# LCD-Shield.net
KiCad netlist of a schematic drawn in EAGLE
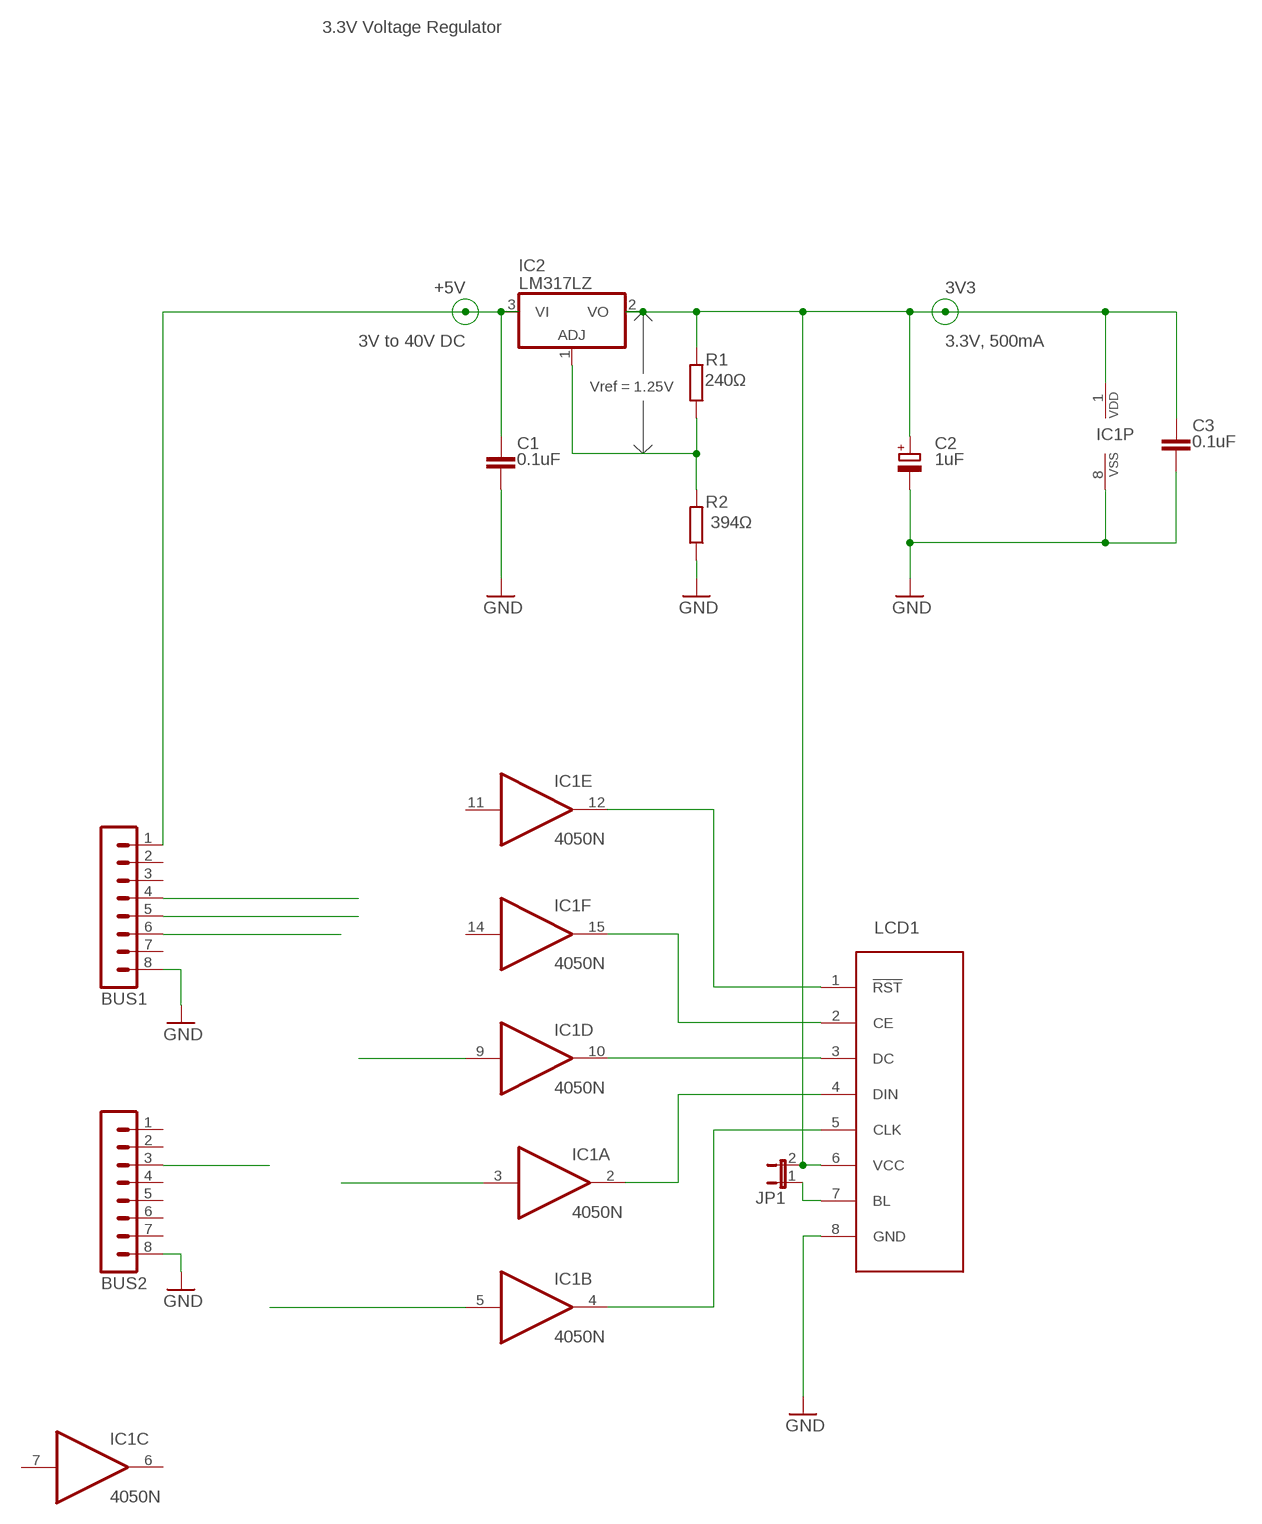
[diagram p0: schematic, sheet 1]

(export (version "E")
  (design (tool "Eeschema 10.0.6"))
  (components
    (comp (ref "BUS1")
      (value "MA08-1")
      (footprint "eagle-import:MA08-1")
      (libsource (lib "eagle-import") (part "MA08-1"))
    )
    (comp (ref "BUS2")
      (value "MA08-1")
      (footprint "eagle-import:MA08-1")
      (libsource (lib "eagle-import") (part "MA08-1"))
    )
    (comp (ref "C1")
      (value "0.1uF")
      (footprint "eagle-import:C025-024X044")
      (libsource (lib "eagle-import") (part "C-EU025-024X044"))
    )
    (comp (ref "C2")
      (value "1uF")
      (footprint "eagle-import:E2-4")
      (libsource (lib "eagle-import") (part "CPOL-EUE2-4"))
    )
    (comp (ref "C3")
      (value "0.1uF")
      (footprint "eagle-import:C025-024X044")
      (libsource (lib "eagle-import") (part "C-EU025-024X044"))
    )
    (comp (ref "IC1")
      (value "4050N")
      (footprint "eagle-import:DIL16")
      (libsource (lib "eagle-import") (part "4050N"))
    )
    (comp (ref "IC2")
      (value "LM317LZ")
      (footprint "eagle-import:TO92")
      (libsource (lib "eagle-import") (part "317LZLM"))
    )
    (comp (ref "JP1")
      (value "JP1E")
      (footprint "eagle-import:JP1")
      (libsource (lib "eagle-import") (part "JP1E"))
    )
    (comp (ref "LCD1")
      (value "5110_LCD_NOKIA")
      (footprint "eagle-import:LCD_5110")
      (libsource (lib "eagle-import") (part "5110_LCD_NOKIA"))
    )
    (comp (ref "R1")
      (value "240Ω")
      (footprint "eagle-import:0207_7")
      (libsource (lib "eagle-import") (part "R-EU_0207/7"))
    )
    (comp (ref "R2")
      (value "394Ω")
      (footprint "eagle-import:0207_7")
      (libsource (lib "eagle-import") (part "R-EU_0207/7"))
    )
  )
  (nets
    (net (code "1") (name "/+5V") (class "Default")
      (node (ref "BUS1") (pin "1") (pinfunction "1_1") (pintype "passive"))
      (node (ref "C1") (pin "1") (pinfunction "1_1") (pintype "passive"))
      (node (ref "IC2") (pin "3") (pinfunction "VI_3") (pintype "input"))
    )
    (net (code "2") (name "/3V3") (class "Default")
      (node (ref "C2") (pin "+") (pinfunction "+_+") (pintype "passive"))
      (node (ref "C3") (pin "1") (pinfunction "1_1") (pintype "passive"))
      (node (ref "IC1") (pin "1") (pinfunction "VDD_1") (pintype "power_in"))
      (node (ref "IC2") (pin "2") (pinfunction "VO_2") (pintype "passive"))
      (node (ref "JP1") (pin "2") (pinfunction "2_2") (pintype "passive"))
      (node (ref "LCD1") (pin "6") (pinfunction "VCC_6") (pintype "bidirectional"))
      (node (ref "R1") (pin "2") (pinfunction "2_2") (pintype "passive"))
    )
    (net (code "3") (name "GND") (class "Default")
      (node (ref "BUS1") (pin "8") (pinfunction "8_8") (pintype "passive"))
      (node (ref "BUS2") (pin "8") (pinfunction "8_8") (pintype "passive"))
      (node (ref "C1") (pin "2") (pinfunction "2_2") (pintype "passive"))
      (node (ref "C2") (pin "-") (pinfunction "-_-") (pintype "passive"))
      (node (ref "C3") (pin "2") (pinfunction "2_2") (pintype "passive"))
      (node (ref "IC1") (pin "8") (pinfunction "VSS_8") (pintype "power_in"))
      (node (ref "LCD1") (pin "8") (pinfunction "GND_8") (pintype "bidirectional"))
      (node (ref "R2") (pin "1") (pinfunction "1_1") (pintype "passive"))
    )
    (net (code "4") (name "Net-(IC1A-O)") (class "Default")
      (node (ref "IC1") (pin "2") (pinfunction "O_2") (pintype "output"))
      (node (ref "LCD1") (pin "4") (pinfunction "DIN_4") (pintype "bidirectional"))
    )
    (net (code "5") (name "Net-(IC1B-O)") (class "Default")
      (node (ref "IC1") (pin "4") (pinfunction "O_4") (pintype "output"))
      (node (ref "LCD1") (pin "5") (pinfunction "CLK_5") (pintype "bidirectional"))
    )
    (net (code "6") (name "Net-(IC1D-O)") (class "Default")
      (node (ref "IC1") (pin "10") (pinfunction "O_10") (pintype "output"))
      (node (ref "LCD1") (pin "3") (pinfunction "DC_3") (pintype "bidirectional"))
    )
    (net (code "7") (name "Net-(IC1E-O)") (class "Default")
      (node (ref "IC1") (pin "12") (pinfunction "O_12") (pintype "output"))
      (node (ref "LCD1") (pin "1") (pinfunction "~{RST}_1") (pintype "bidirectional"))
    )
    (net (code "8") (name "Net-(IC1F-O)") (class "Default")
      (node (ref "IC1") (pin "15") (pinfunction "O_15") (pintype "output"))
      (node (ref "LCD1") (pin "2") (pinfunction "CE_2") (pintype "bidirectional"))
    )
    (net (code "9") (name "Net-(IC2-ADJ)") (class "Default")
      (node (ref "IC2") (pin "1") (pinfunction "ADJ_1") (pintype "input"))
      (node (ref "R1") (pin "1") (pinfunction "1_1") (pintype "passive"))
      (node (ref "R2") (pin "2") (pinfunction "2_2") (pintype "passive"))
    )
    (net (code "10") (name "Net-(LCD1-BL)") (class "Default")
      (node (ref "JP1") (pin "1") (pinfunction "1_1") (pintype "passive"))
      (node (ref "LCD1") (pin "7") (pinfunction "BL_7") (pintype "bidirectional"))
    )
    (net (code "11") (name "unconnected-(BUS1-Pad2)") (class "Default")
      (node (ref "BUS1") (pin "2") (pinfunction "2_2") (pintype "passive"))
    )
    (net (code "12") (name "unconnected-(BUS1-Pad3)") (class "Default")
      (node (ref "BUS1") (pin "3") (pinfunction "3_3") (pintype "passive"))
    )
    (net (code "13") (name "unconnected-(BUS1-Pad4)") (class "Default")
      (node (ref "BUS1") (pin "4") (pinfunction "4_4") (pintype "passive"))
    )
    (net (code "14") (name "unconnected-(BUS1-Pad5)") (class "Default")
      (node (ref "BUS1") (pin "5") (pinfunction "5_5") (pintype "passive"))
    )
    (net (code "15") (name "unconnected-(BUS1-Pad6)") (class "Default")
      (node (ref "BUS1") (pin "6") (pinfunction "6_6") (pintype "passive"))
    )
    (net (code "16") (name "unconnected-(BUS1-Pad7)") (class "Default")
      (node (ref "BUS1") (pin "7") (pinfunction "7_7") (pintype "passive"))
    )
    (net (code "17") (name "unconnected-(BUS2-Pad1)") (class "Default")
      (node (ref "BUS2") (pin "1") (pinfunction "1_1") (pintype "passive"))
    )
    (net (code "18") (name "unconnected-(BUS2-Pad2)") (class "Default")
      (node (ref "BUS2") (pin "2") (pinfunction "2_2") (pintype "passive"))
    )
    (net (code "19") (name "unconnected-(BUS2-Pad3)") (class "Default")
      (node (ref "BUS2") (pin "3") (pinfunction "3_3") (pintype "passive"))
    )
    (net (code "20") (name "unconnected-(BUS2-Pad4)") (class "Default")
      (node (ref "BUS2") (pin "4") (pinfunction "4_4") (pintype "passive"))
    )
    (net (code "21") (name "unconnected-(BUS2-Pad5)") (class "Default")
      (node (ref "BUS2") (pin "5") (pinfunction "5_5") (pintype "passive"))
    )
    (net (code "22") (name "unconnected-(BUS2-Pad6)") (class "Default")
      (node (ref "BUS2") (pin "6") (pinfunction "6_6") (pintype "passive"))
    )
    (net (code "23") (name "unconnected-(BUS2-Pad7)") (class "Default")
      (node (ref "BUS2") (pin "7") (pinfunction "7_7") (pintype "passive"))
    )
    (net (code "24") (name "unconnected-(IC1A-I-Pad3)") (class "Default")
      (node (ref "IC1") (pin "3") (pinfunction "I_3") (pintype "input"))
    )
    (net (code "25") (name "unconnected-(IC1B-I-Pad5)") (class "Default")
      (node (ref "IC1") (pin "5") (pinfunction "I_5") (pintype "input"))
    )
    (net (code "26") (name "unconnected-(IC1C-I-Pad7)") (class "Default")
      (node (ref "IC1") (pin "7") (pinfunction "I_7") (pintype "input"))
    )
    (net (code "27") (name "unconnected-(IC1C-O-Pad6)") (class "Default")
      (node (ref "IC1") (pin "6") (pinfunction "O_6") (pintype "output"))
    )
    (net (code "28") (name "unconnected-(IC1D-I-Pad9)") (class "Default")
      (node (ref "IC1") (pin "9") (pinfunction "I_9") (pintype "input"))
    )
    (net (code "29") (name "unconnected-(IC1E-I-Pad11)") (class "Default")
      (node (ref "IC1") (pin "11") (pinfunction "I_11") (pintype "input"))
    )
    (net (code "30") (name "unconnected-(IC1F-I-Pad14)") (class "Default")
      (node (ref "IC1") (pin "14") (pinfunction "I_14") (pintype "input"))
    )
  )
)
